# dma-module.net
KiCad netlist of a schematic drawn in EAGLE
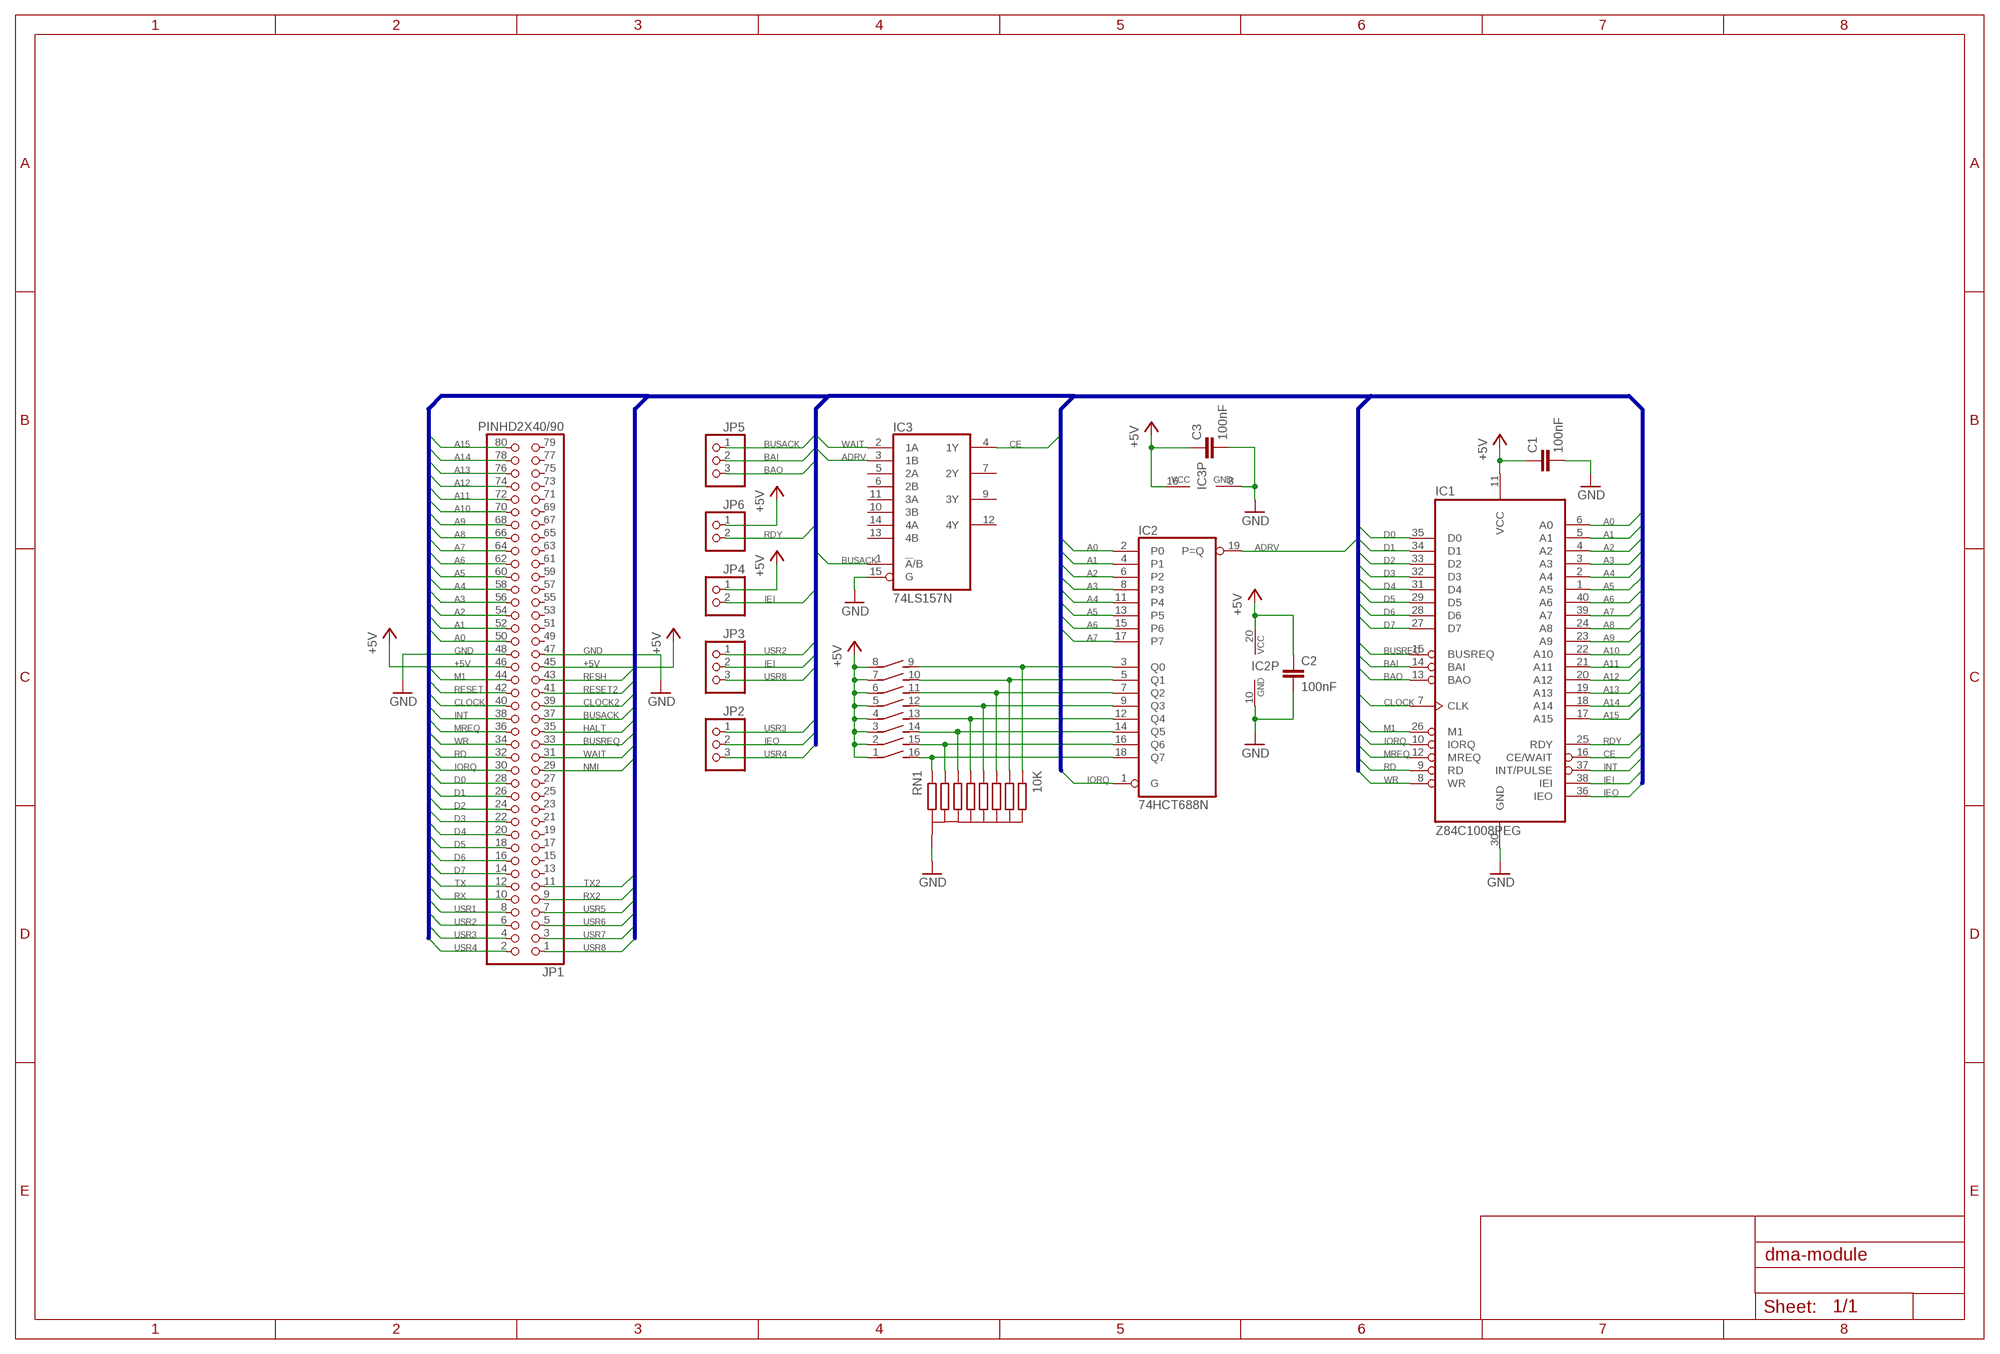
[diagram p0: schematic, sheet 1]

(export (version "E")
  (design (tool "Eeschema 10.0.6"))
  (components
    (comp (ref "C1")
      (value "100nF")
      (footprint "eagle-import:C025-025X050")
      (libsource (lib "eagle-import") (part "C-EU025-025X050"))
    )
    (comp (ref "C2")
      (value "100nF")
      (footprint "eagle-import:C025-025X050")
      (libsource (lib "eagle-import") (part "C-EU025-025X050"))
    )
    (comp (ref "C3")
      (value "100nF")
      (footprint "eagle-import:C025-025X050")
      (libsource (lib "eagle-import") (part "C-EU025-025X050"))
    )
    (comp (ref "IC1")
      (value "Z84C1008PEG")
      (footprint "eagle-import:DIP40")
      (libsource (lib "eagle-import") (part "Z84C1008PEG"))
    )
    (comp (ref "IC2")
      (value "74HCT688N")
      (footprint "eagle-import:DIL20")
      (libsource (lib "eagle-import") (part "74688NHCT"))
    )
    (comp (ref "IC3")
      (value "74LS157N")
      (footprint "eagle-import:DIL16")
      (libsource (lib "eagle-import") (part "74157NLS"))
    )
    (comp (ref "JP1")
      (value "PINHD2X40/90")
      (footprint "eagle-import:2X40_90")
      (libsource (lib "eagle-import") (part "PINHD2X40/90"))
    )
    (comp (ref "JP2")
      (value "PINHD-1X3/90")
      (footprint "eagle-import:1X03_90")
      (libsource (lib "eagle-import") (part "PINHD-1X3/90"))
    )
    (comp (ref "JP3")
      (value "PINHD-1X3/90")
      (footprint "eagle-import:1X03_90")
      (libsource (lib "eagle-import") (part "PINHD-1X3/90"))
    )
    (comp (ref "JP4")
      (value "PINHD-1X2/90")
      (footprint "eagle-import:1X02_90")
      (libsource (lib "eagle-import") (part "PINHD-1X2/90"))
    )
    (comp (ref "JP5")
      (value "PINHD-1X3/90")
      (footprint "eagle-import:1X03_90")
      (libsource (lib "eagle-import") (part "PINHD-1X3/90"))
    )
    (comp (ref "JP6")
      (value "PINHD-1X2/90")
      (footprint "eagle-import:1X02_90")
      (libsource (lib "eagle-import") (part "PINHD-1X2/90"))
    )
    (comp (ref "RN1")
      (value "10K")
      (footprint "eagle-import:RBUS")
      (libsource (lib "eagle-import") (part "RBUS"))
    )
    (comp (ref "S1")
      (value "DIP08SB")
      (footprint "eagle-import:DIP08SB")
      (libsource (lib "eagle-import") (part "DIP08SB"))
    )
  )
  (nets
    (net (code "1") (name "+5V") (class "Default")
      (node (ref "C1") (pin "1") (pinfunction "1_1") (pintype "passive"))
      (node (ref "C2") (pin "1") (pinfunction "1_1") (pintype "passive"))
      (node (ref "C3") (pin "1") (pinfunction "1_1") (pintype "passive"))
      (node (ref "IC1") (pin "11") (pinfunction "VCC_11") (pintype "power_in"))
      (node (ref "IC2") (pin "20") (pinfunction "VCC_20") (pintype "power_in"))
      (node (ref "IC3") (pin "16") (pinfunction "VCC_16") (pintype "power_in"))
      (node (ref "JP1") (pin "45") (pinfunction "45_45") (pintype "passive"))
      (node (ref "JP1") (pin "46") (pinfunction "46_46") (pintype "passive"))
      (node (ref "JP4") (pin "1") (pinfunction "1_1") (pintype "passive"))
      (node (ref "JP6") (pin "1") (pinfunction "1_1") (pintype "passive"))
      (node (ref "S1") (pin "1") (pinfunction "1_1") (pintype "passive"))
      (node (ref "S1") (pin "2") (pinfunction "1_2") (pintype "passive"))
      (node (ref "S1") (pin "3") (pinfunction "1_3") (pintype "passive"))
      (node (ref "S1") (pin "4") (pinfunction "1_4") (pintype "passive"))
      (node (ref "S1") (pin "5") (pinfunction "1_5") (pintype "passive"))
      (node (ref "S1") (pin "6") (pinfunction "1_6") (pintype "passive"))
      (node (ref "S1") (pin "7") (pinfunction "1_7") (pintype "passive"))
      (node (ref "S1") (pin "8") (pinfunction "1_8") (pintype "passive"))
    )
    (net (code "2") (name "/A0") (class "Default")
      (node (ref "IC1") (pin "6") (pinfunction "A0_6") (pintype "output"))
      (node (ref "IC2") (pin "2") (pinfunction "P0_2") (pintype "input"))
      (node (ref "JP1") (pin "50") (pinfunction "50_50") (pintype "passive"))
    )
    (net (code "3") (name "/A1") (class "Default")
      (node (ref "IC1") (pin "5") (pinfunction "A1_5") (pintype "output"))
      (node (ref "IC2") (pin "4") (pinfunction "P1_4") (pintype "input"))
      (node (ref "JP1") (pin "52") (pinfunction "52_52") (pintype "passive"))
    )
    (net (code "4") (name "/A2") (class "Default")
      (node (ref "IC1") (pin "4") (pinfunction "A2_4") (pintype "output"))
      (node (ref "IC2") (pin "6") (pinfunction "P2_6") (pintype "input"))
      (node (ref "JP1") (pin "54") (pinfunction "54_54") (pintype "passive"))
    )
    (net (code "5") (name "/A3") (class "Default")
      (node (ref "IC1") (pin "3") (pinfunction "A3_3") (pintype "output"))
      (node (ref "IC2") (pin "8") (pinfunction "P3_8") (pintype "input"))
      (node (ref "JP1") (pin "56") (pinfunction "56_56") (pintype "passive"))
    )
    (net (code "6") (name "/A4") (class "Default")
      (node (ref "IC1") (pin "2") (pinfunction "A4_2") (pintype "output"))
      (node (ref "IC2") (pin "11") (pinfunction "P4_11") (pintype "input"))
      (node (ref "JP1") (pin "58") (pinfunction "58_58") (pintype "passive"))
    )
    (net (code "7") (name "/A5") (class "Default")
      (node (ref "IC1") (pin "1") (pinfunction "A5_1") (pintype "output"))
      (node (ref "IC2") (pin "13") (pinfunction "P5_13") (pintype "input"))
      (node (ref "JP1") (pin "60") (pinfunction "60_60") (pintype "passive"))
    )
    (net (code "8") (name "/A6") (class "Default")
      (node (ref "IC1") (pin "40") (pinfunction "A6_40") (pintype "output"))
      (node (ref "IC2") (pin "15") (pinfunction "P6_15") (pintype "input"))
      (node (ref "JP1") (pin "62") (pinfunction "62_62") (pintype "passive"))
    )
    (net (code "9") (name "/A7") (class "Default")
      (node (ref "IC1") (pin "39") (pinfunction "A7_39") (pintype "output"))
      (node (ref "IC2") (pin "17") (pinfunction "P7_17") (pintype "input"))
      (node (ref "JP1") (pin "64") (pinfunction "64_64") (pintype "passive"))
    )
    (net (code "10") (name "/A8") (class "Default")
      (node (ref "IC1") (pin "24") (pinfunction "A8_24") (pintype "output"))
      (node (ref "JP1") (pin "66") (pinfunction "66_66") (pintype "passive"))
    )
    (net (code "11") (name "/A9") (class "Default")
      (node (ref "IC1") (pin "23") (pinfunction "A9_23") (pintype "output"))
      (node (ref "JP1") (pin "68") (pinfunction "68_68") (pintype "passive"))
    )
    (net (code "12") (name "/A10") (class "Default")
      (node (ref "IC1") (pin "22") (pinfunction "A10_22") (pintype "output"))
      (node (ref "JP1") (pin "70") (pinfunction "70_70") (pintype "passive"))
    )
    (net (code "13") (name "/A11") (class "Default")
      (node (ref "IC1") (pin "21") (pinfunction "A11_21") (pintype "output"))
      (node (ref "JP1") (pin "72") (pinfunction "72_72") (pintype "passive"))
    )
    (net (code "14") (name "/A12") (class "Default")
      (node (ref "IC1") (pin "20") (pinfunction "A12_20") (pintype "output"))
      (node (ref "JP1") (pin "74") (pinfunction "74_74") (pintype "passive"))
    )
    (net (code "15") (name "/A13") (class "Default")
      (node (ref "IC1") (pin "19") (pinfunction "A13_19") (pintype "output"))
      (node (ref "JP1") (pin "76") (pinfunction "76_76") (pintype "passive"))
    )
    (net (code "16") (name "/A14") (class "Default")
      (node (ref "IC1") (pin "18") (pinfunction "A14_18") (pintype "output"))
      (node (ref "JP1") (pin "78") (pinfunction "78_78") (pintype "passive"))
    )
    (net (code "17") (name "/A15") (class "Default")
      (node (ref "IC1") (pin "17") (pinfunction "A15_17") (pintype "output"))
      (node (ref "JP1") (pin "80") (pinfunction "80_80") (pintype "passive"))
    )
    (net (code "18") (name "/ADRV") (class "Default")
      (node (ref "IC2") (pin "19") (pinfunction "P=Q_19") (pintype "output"))
      (node (ref "IC3") (pin "3") (pinfunction "1B_3") (pintype "input"))
    )
    (net (code "19") (name "/BAI") (class "Default")
      (node (ref "IC1") (pin "14") (pinfunction "BAI_14") (pintype "input"))
      (node (ref "JP5") (pin "2") (pinfunction "2_2") (pintype "passive"))
    )
    (net (code "20") (name "/BAO") (class "Default")
      (node (ref "IC1") (pin "13") (pinfunction "BAO_13") (pintype "output"))
      (node (ref "JP5") (pin "3") (pinfunction "3_3") (pintype "passive"))
    )
    (net (code "21") (name "/BUSACK") (class "Default")
      (node (ref "IC3") (pin "1") (pinfunction "~{A}/B_1") (pintype "input"))
      (node (ref "JP1") (pin "37") (pinfunction "37_37") (pintype "passive"))
      (node (ref "JP5") (pin "1") (pinfunction "1_1") (pintype "passive"))
    )
    (net (code "22") (name "/BUSREQ") (class "Default")
      (node (ref "IC1") (pin "15") (pinfunction "BUSREQ_15") (pintype "bidirectional"))
      (node (ref "JP1") (pin "33") (pinfunction "33_33") (pintype "passive"))
    )
    (net (code "23") (name "/CE") (class "Default")
      (node (ref "IC1") (pin "16") (pinfunction "CE/WAIT_16") (pintype "input"))
      (node (ref "IC3") (pin "4") (pinfunction "1Y_4") (pintype "output"))
    )
    (net (code "24") (name "/CLOCK") (class "Default")
      (node (ref "IC1") (pin "7") (pinfunction "CLK_7") (pintype "input"))
      (node (ref "JP1") (pin "40") (pinfunction "40_40") (pintype "passive"))
    )
    (net (code "25") (name "/CLOCK2") (class "Default")
      (node (ref "JP1") (pin "39") (pinfunction "39_39") (pintype "passive"))
    )
    (net (code "26") (name "/D0") (class "Default")
      (node (ref "IC1") (pin "35") (pinfunction "D0_35") (pintype "bidirectional"))
      (node (ref "JP1") (pin "28") (pinfunction "28_28") (pintype "passive"))
    )
    (net (code "27") (name "/D1") (class "Default")
      (node (ref "IC1") (pin "34") (pinfunction "D1_34") (pintype "bidirectional"))
      (node (ref "JP1") (pin "26") (pinfunction "26_26") (pintype "passive"))
    )
    (net (code "28") (name "/D2") (class "Default")
      (node (ref "IC1") (pin "33") (pinfunction "D2_33") (pintype "bidirectional"))
      (node (ref "JP1") (pin "24") (pinfunction "24_24") (pintype "passive"))
    )
    (net (code "29") (name "/D3") (class "Default")
      (node (ref "IC1") (pin "32") (pinfunction "D3_32") (pintype "bidirectional"))
      (node (ref "JP1") (pin "22") (pinfunction "22_22") (pintype "passive"))
    )
    (net (code "30") (name "/D4") (class "Default")
      (node (ref "IC1") (pin "31") (pinfunction "D4_31") (pintype "bidirectional"))
      (node (ref "JP1") (pin "20") (pinfunction "20_20") (pintype "passive"))
    )
    (net (code "31") (name "/D5") (class "Default")
      (node (ref "IC1") (pin "29") (pinfunction "D5_29") (pintype "bidirectional"))
      (node (ref "JP1") (pin "18") (pinfunction "18_18") (pintype "passive"))
    )
    (net (code "32") (name "/D6") (class "Default")
      (node (ref "IC1") (pin "28") (pinfunction "D6_28") (pintype "bidirectional"))
      (node (ref "JP1") (pin "16") (pinfunction "16_16") (pintype "passive"))
    )
    (net (code "33") (name "/D7") (class "Default")
      (node (ref "IC1") (pin "27") (pinfunction "D7_27") (pintype "bidirectional"))
      (node (ref "JP1") (pin "14") (pinfunction "14_14") (pintype "passive"))
    )
    (net (code "34") (name "/HALT") (class "Default")
      (node (ref "JP1") (pin "35") (pinfunction "35_35") (pintype "passive"))
    )
    (net (code "35") (name "/IEI") (class "Default")
      (node (ref "IC1") (pin "38") (pinfunction "IEI_38") (pintype "input"))
      (node (ref "JP3") (pin "2") (pinfunction "2_2") (pintype "passive"))
      (node (ref "JP4") (pin "2") (pinfunction "2_2") (pintype "passive"))
    )
    (net (code "36") (name "/IEO") (class "Default")
      (node (ref "IC1") (pin "36") (pinfunction "IEO_36") (pintype "output"))
      (node (ref "JP2") (pin "2") (pinfunction "2_2") (pintype "passive"))
    )
    (net (code "37") (name "/INT") (class "Default")
      (node (ref "IC1") (pin "37") (pinfunction "INT/PULSE_37") (pintype "output"))
      (node (ref "JP1") (pin "38") (pinfunction "38_38") (pintype "passive"))
    )
    (net (code "38") (name "/IORQ") (class "Default")
      (node (ref "IC1") (pin "10") (pinfunction "IORQ_10") (pintype "bidirectional"))
      (node (ref "IC2") (pin "1") (pinfunction "G_1") (pintype "input"))
      (node (ref "JP1") (pin "30") (pinfunction "30_30") (pintype "passive"))
    )
    (net (code "39") (name "/M1") (class "Default")
      (node (ref "IC1") (pin "26") (pinfunction "M1_26") (pintype "input"))
      (node (ref "JP1") (pin "44") (pinfunction "44_44") (pintype "passive"))
    )
    (net (code "40") (name "/MREQ") (class "Default")
      (node (ref "IC1") (pin "12") (pinfunction "MREQ_12") (pintype "output"))
      (node (ref "JP1") (pin "36") (pinfunction "36_36") (pintype "passive"))
    )
    (net (code "41") (name "/NMI") (class "Default")
      (node (ref "JP1") (pin "29") (pinfunction "29_29") (pintype "passive"))
    )
    (net (code "42") (name "/RD") (class "Default")
      (node (ref "IC1") (pin "9") (pinfunction "RD_9") (pintype "bidirectional"))
      (node (ref "JP1") (pin "32") (pinfunction "32_32") (pintype "passive"))
    )
    (net (code "43") (name "/RDY") (class "Default")
      (node (ref "IC1") (pin "25") (pinfunction "RDY_25") (pintype "input"))
      (node (ref "JP6") (pin "2") (pinfunction "2_2") (pintype "passive"))
    )
    (net (code "44") (name "/RESET") (class "Default")
      (node (ref "JP1") (pin "42") (pinfunction "42_42") (pintype "passive"))
    )
    (net (code "45") (name "/RESET2") (class "Default")
      (node (ref "JP1") (pin "41") (pinfunction "41_41") (pintype "passive"))
    )
    (net (code "46") (name "/RFSH") (class "Default")
      (node (ref "JP1") (pin "43") (pinfunction "43_43") (pintype "passive"))
    )
    (net (code "47") (name "/RX") (class "Default")
      (node (ref "JP1") (pin "10") (pinfunction "10_10") (pintype "passive"))
    )
    (net (code "48") (name "/RX2") (class "Default")
      (node (ref "JP1") (pin "9") (pinfunction "9_9") (pintype "passive"))
    )
    (net (code "49") (name "/TX") (class "Default")
      (node (ref "JP1") (pin "12") (pinfunction "12_12") (pintype "passive"))
    )
    (net (code "50") (name "/TX2") (class "Default")
      (node (ref "JP1") (pin "11") (pinfunction "11_11") (pintype "passive"))
    )
    (net (code "51") (name "/USR1") (class "Default")
      (node (ref "JP1") (pin "8") (pinfunction "8_8") (pintype "passive"))
    )
    (net (code "52") (name "/USR2") (class "Default")
      (node (ref "JP1") (pin "6") (pinfunction "6_6") (pintype "passive"))
      (node (ref "JP3") (pin "1") (pinfunction "1_1") (pintype "passive"))
    )
    (net (code "53") (name "/USR3") (class "Default")
      (node (ref "JP1") (pin "4") (pinfunction "4_4") (pintype "passive"))
      (node (ref "JP2") (pin "1") (pinfunction "1_1") (pintype "passive"))
    )
    (net (code "54") (name "/USR4") (class "Default")
      (node (ref "JP1") (pin "2") (pinfunction "2_2") (pintype "passive"))
      (node (ref "JP2") (pin "3") (pinfunction "3_3") (pintype "passive"))
    )
    (net (code "55") (name "/USR5") (class "Default")
      (node (ref "JP1") (pin "7") (pinfunction "7_7") (pintype "passive"))
    )
    (net (code "56") (name "/USR6") (class "Default")
      (node (ref "JP1") (pin "5") (pinfunction "5_5") (pintype "passive"))
    )
    (net (code "57") (name "/USR7") (class "Default")
      (node (ref "JP1") (pin "3") (pinfunction "3_3") (pintype "passive"))
    )
    (net (code "58") (name "/USR8") (class "Default")
      (node (ref "JP1") (pin "1") (pinfunction "1_1") (pintype "passive"))
      (node (ref "JP3") (pin "3") (pinfunction "3_3") (pintype "passive"))
    )
    (net (code "59") (name "/WAIT") (class "Default")
      (node (ref "IC3") (pin "2") (pinfunction "1A_2") (pintype "input"))
      (node (ref "JP1") (pin "31") (pinfunction "31_31") (pintype "passive"))
    )
    (net (code "60") (name "/WR") (class "Default")
      (node (ref "IC1") (pin "8") (pinfunction "WR_8") (pintype "bidirectional"))
      (node (ref "JP1") (pin "34") (pinfunction "34_34") (pintype "passive"))
    )
    (net (code "61") (name "GND") (class "Default")
      (node (ref "C1") (pin "2") (pinfunction "2_2") (pintype "passive"))
      (node (ref "C2") (pin "2") (pinfunction "2_2") (pintype "passive"))
      (node (ref "C3") (pin "2") (pinfunction "2_2") (pintype "passive"))
      (node (ref "IC1") (pin "30") (pinfunction "GND_30") (pintype "power_in"))
      (node (ref "IC2") (pin "10") (pinfunction "GND_10") (pintype "power_in"))
      (node (ref "IC3") (pin "15") (pinfunction "G_15") (pintype "input"))
      (node (ref "IC3") (pin "8") (pinfunction "GND_8") (pintype "power_in"))
      (node (ref "JP1") (pin "47") (pinfunction "47_47") (pintype "passive"))
      (node (ref "JP1") (pin "48") (pinfunction "48_48") (pintype "passive"))
      (node (ref "RN1") (pin "P$1") (pinfunction "COM_P$1") (pintype "output"))
    )
    (net (code "62") (name "Net-(IC2A-Q0)") (class "Default")
      (node (ref "IC2") (pin "3") (pinfunction "Q0_3") (pintype "input"))
      (node (ref "RN1") (pin "P$9") (pinfunction "R8_P$9") (pintype "output"))
      (node (ref "S1") (pin "9") (pinfunction "2_9") (pintype "passive"))
    )
    (net (code "63") (name "Net-(IC2A-Q1)") (class "Default")
      (node (ref "IC2") (pin "5") (pinfunction "Q1_5") (pintype "input"))
      (node (ref "RN1") (pin "P$8") (pinfunction "R7_P$8") (pintype "output"))
      (node (ref "S1") (pin "10") (pinfunction "2_10") (pintype "passive"))
    )
    (net (code "64") (name "Net-(IC2A-Q2)") (class "Default")
      (node (ref "IC2") (pin "7") (pinfunction "Q2_7") (pintype "input"))
      (node (ref "RN1") (pin "P$7") (pinfunction "R6_P$7") (pintype "output"))
      (node (ref "S1") (pin "11") (pinfunction "2_11") (pintype "passive"))
    )
    (net (code "65") (name "Net-(IC2A-Q3)") (class "Default")
      (node (ref "IC2") (pin "9") (pinfunction "Q3_9") (pintype "input"))
      (node (ref "RN1") (pin "P$6") (pinfunction "R5_P$6") (pintype "output"))
      (node (ref "S1") (pin "12") (pinfunction "2_12") (pintype "passive"))
    )
    (net (code "66") (name "Net-(IC2A-Q4)") (class "Default")
      (node (ref "IC2") (pin "12") (pinfunction "Q4_12") (pintype "input"))
      (node (ref "RN1") (pin "P$5") (pinfunction "R4_P$5") (pintype "output"))
      (node (ref "S1") (pin "13") (pinfunction "2_13") (pintype "passive"))
    )
    (net (code "67") (name "Net-(IC2A-Q5)") (class "Default")
      (node (ref "IC2") (pin "14") (pinfunction "Q5_14") (pintype "input"))
      (node (ref "RN1") (pin "P$4") (pinfunction "R3_P$4") (pintype "output"))
      (node (ref "S1") (pin "14") (pinfunction "2_14") (pintype "passive"))
    )
    (net (code "68") (name "Net-(IC2A-Q6)") (class "Default")
      (node (ref "IC2") (pin "16") (pinfunction "Q6_16") (pintype "input"))
      (node (ref "RN1") (pin "P$3") (pinfunction "R2_P$3") (pintype "output"))
      (node (ref "S1") (pin "15") (pinfunction "2_15") (pintype "passive"))
    )
    (net (code "69") (name "Net-(IC2A-Q7)") (class "Default")
      (node (ref "IC2") (pin "18") (pinfunction "Q7_18") (pintype "input"))
      (node (ref "RN1") (pin "P$2") (pinfunction "R1_P$2") (pintype "output"))
      (node (ref "S1") (pin "16") (pinfunction "2_16") (pintype "passive"))
    )
    (net (code "70") (name "unconnected-(IC3A-2A-Pad5)") (class "Default")
      (node (ref "IC3") (pin "5") (pinfunction "2A_5") (pintype "input"))
    )
    (net (code "71") (name "unconnected-(IC3A-2B-Pad6)") (class "Default")
      (node (ref "IC3") (pin "6") (pinfunction "2B_6") (pintype "input"))
    )
    (net (code "72") (name "unconnected-(IC3A-2Y-Pad7)") (class "Default")
      (node (ref "IC3") (pin "7") (pinfunction "2Y_7") (pintype "output"))
    )
    (net (code "73") (name "unconnected-(IC3A-3A-Pad11)") (class "Default")
      (node (ref "IC3") (pin "11") (pinfunction "3A_11") (pintype "input"))
    )
    (net (code "74") (name "unconnected-(IC3A-3B-Pad10)") (class "Default")
      (node (ref "IC3") (pin "10") (pinfunction "3B_10") (pintype "input"))
    )
    (net (code "75") (name "unconnected-(IC3A-3Y-Pad9)") (class "Default")
      (node (ref "IC3") (pin "9") (pinfunction "3Y_9") (pintype "output"))
    )
    (net (code "76") (name "unconnected-(IC3A-4A-Pad14)") (class "Default")
      (node (ref "IC3") (pin "14") (pinfunction "4A_14") (pintype "input"))
    )
    (net (code "77") (name "unconnected-(IC3A-4B-Pad13)") (class "Default")
      (node (ref "IC3") (pin "13") (pinfunction "4B_13") (pintype "input"))
    )
    (net (code "78") (name "unconnected-(IC3A-4Y-Pad12)") (class "Default")
      (node (ref "IC3") (pin "12") (pinfunction "4Y_12") (pintype "output"))
    )
    (net (code "79") (name "unconnected-(JP1-Pad13)") (class "Default")
      (node (ref "JP1") (pin "13") (pinfunction "13_13") (pintype "passive"))
    )
    (net (code "80") (name "unconnected-(JP1-Pad15)") (class "Default")
      (node (ref "JP1") (pin "15") (pinfunction "15_15") (pintype "passive"))
    )
    (net (code "81") (name "unconnected-(JP1-Pad17)") (class "Default")
      (node (ref "JP1") (pin "17") (pinfunction "17_17") (pintype "passive"))
    )
    (net (code "82") (name "unconnected-(JP1-Pad19)") (class "Default")
      (node (ref "JP1") (pin "19") (pinfunction "19_19") (pintype "passive"))
    )
    (net (code "83") (name "unconnected-(JP1-Pad21)") (class "Default")
      (node (ref "JP1") (pin "21") (pinfunction "21_21") (pintype "passive"))
    )
    (net (code "84") (name "unconnected-(JP1-Pad23)") (class "Default")
      (node (ref "JP1") (pin "23") (pinfunction "23_23") (pintype "passive"))
    )
    (net (code "85") (name "unconnected-(JP1-Pad25)") (class "Default")
      (node (ref "JP1") (pin "25") (pinfunction "25_25") (pintype "passive"))
    )
    (net (code "86") (name "unconnected-(JP1-Pad27)") (class "Default")
      (node (ref "JP1") (pin "27") (pinfunction "27_27") (pintype "passive"))
    )
    (net (code "87") (name "unconnected-(JP1-Pad49)") (class "Default")
      (node (ref "JP1") (pin "49") (pinfunction "49_49") (pintype "passive"))
    )
    (net (code "88") (name "unconnected-(JP1-Pad51)") (class "Default")
      (node (ref "JP1") (pin "51") (pinfunction "51_51") (pintype "passive"))
    )
    (net (code "89") (name "unconnected-(JP1-Pad53)") (class "Default")
      (node (ref "JP1") (pin "53") (pinfunction "53_53") (pintype "passive"))
    )
    (net (code "90") (name "unconnected-(JP1-Pad55)") (class "Default")
      (node (ref "JP1") (pin "55") (pinfunction "55_55") (pintype "passive"))
    )
    (net (code "91") (name "unconnected-(JP1-Pad57)") (class "Default")
      (node (ref "JP1") (pin "57") (pinfunction "57_57") (pintype "passive"))
    )
    (net (code "92") (name "unconnected-(JP1-Pad59)") (class "Default")
      (node (ref "JP1") (pin "59") (pinfunction "59_59") (pintype "passive"))
    )
    (net (code "93") (name "unconnected-(JP1-Pad61)") (class "Default")
      (node (ref "JP1") (pin "61") (pinfunction "61_61") (pintype "passive"))
    )
    (net (code "94") (name "unconnected-(JP1-Pad63)") (class "Default")
      (node (ref "JP1") (pin "63") (pinfunction "63_63") (pintype "passive"))
    )
    (net (code "95") (name "unconnected-(JP1-Pad65)") (class "Default")
      (node (ref "JP1") (pin "65") (pinfunction "65_65") (pintype "passive"))
    )
    (net (code "96") (name "unconnected-(JP1-Pad67)") (class "Default")
      (node (ref "JP1") (pin "67") (pinfunction "67_67") (pintype "passive"))
    )
    (net (code "97") (name "unconnected-(JP1-Pad69)") (class "Default")
      (node (ref "JP1") (pin "69") (pinfunction "69_69") (pintype "passive"))
    )
    (net (code "98") (name "unconnected-(JP1-Pad71)") (class "Default")
      (node (ref "JP1") (pin "71") (pinfunction "71_71") (pintype "passive"))
    )
    (net (code "99") (name "unconnected-(JP1-Pad73)") (class "Default")
      (node (ref "JP1") (pin "73") (pinfunction "73_73") (pintype "passive"))
    )
    (net (code "100") (name "unconnected-(JP1-Pad75)") (class "Default")
      (node (ref "JP1") (pin "75") (pinfunction "75_75") (pintype "passive"))
    )
    (net (code "101") (name "unconnected-(JP1-Pad77)") (class "Default")
      (node (ref "JP1") (pin "77") (pinfunction "77_77") (pintype "passive"))
    )
    (net (code "102") (name "unconnected-(JP1-Pad79)") (class "Default")
      (node (ref "JP1") (pin "79") (pinfunction "79_79") (pintype "passive"))
    )
  )
)
